# MPL3115A2_breakout.net
KiCad netlist of a schematic drawn in EAGLE
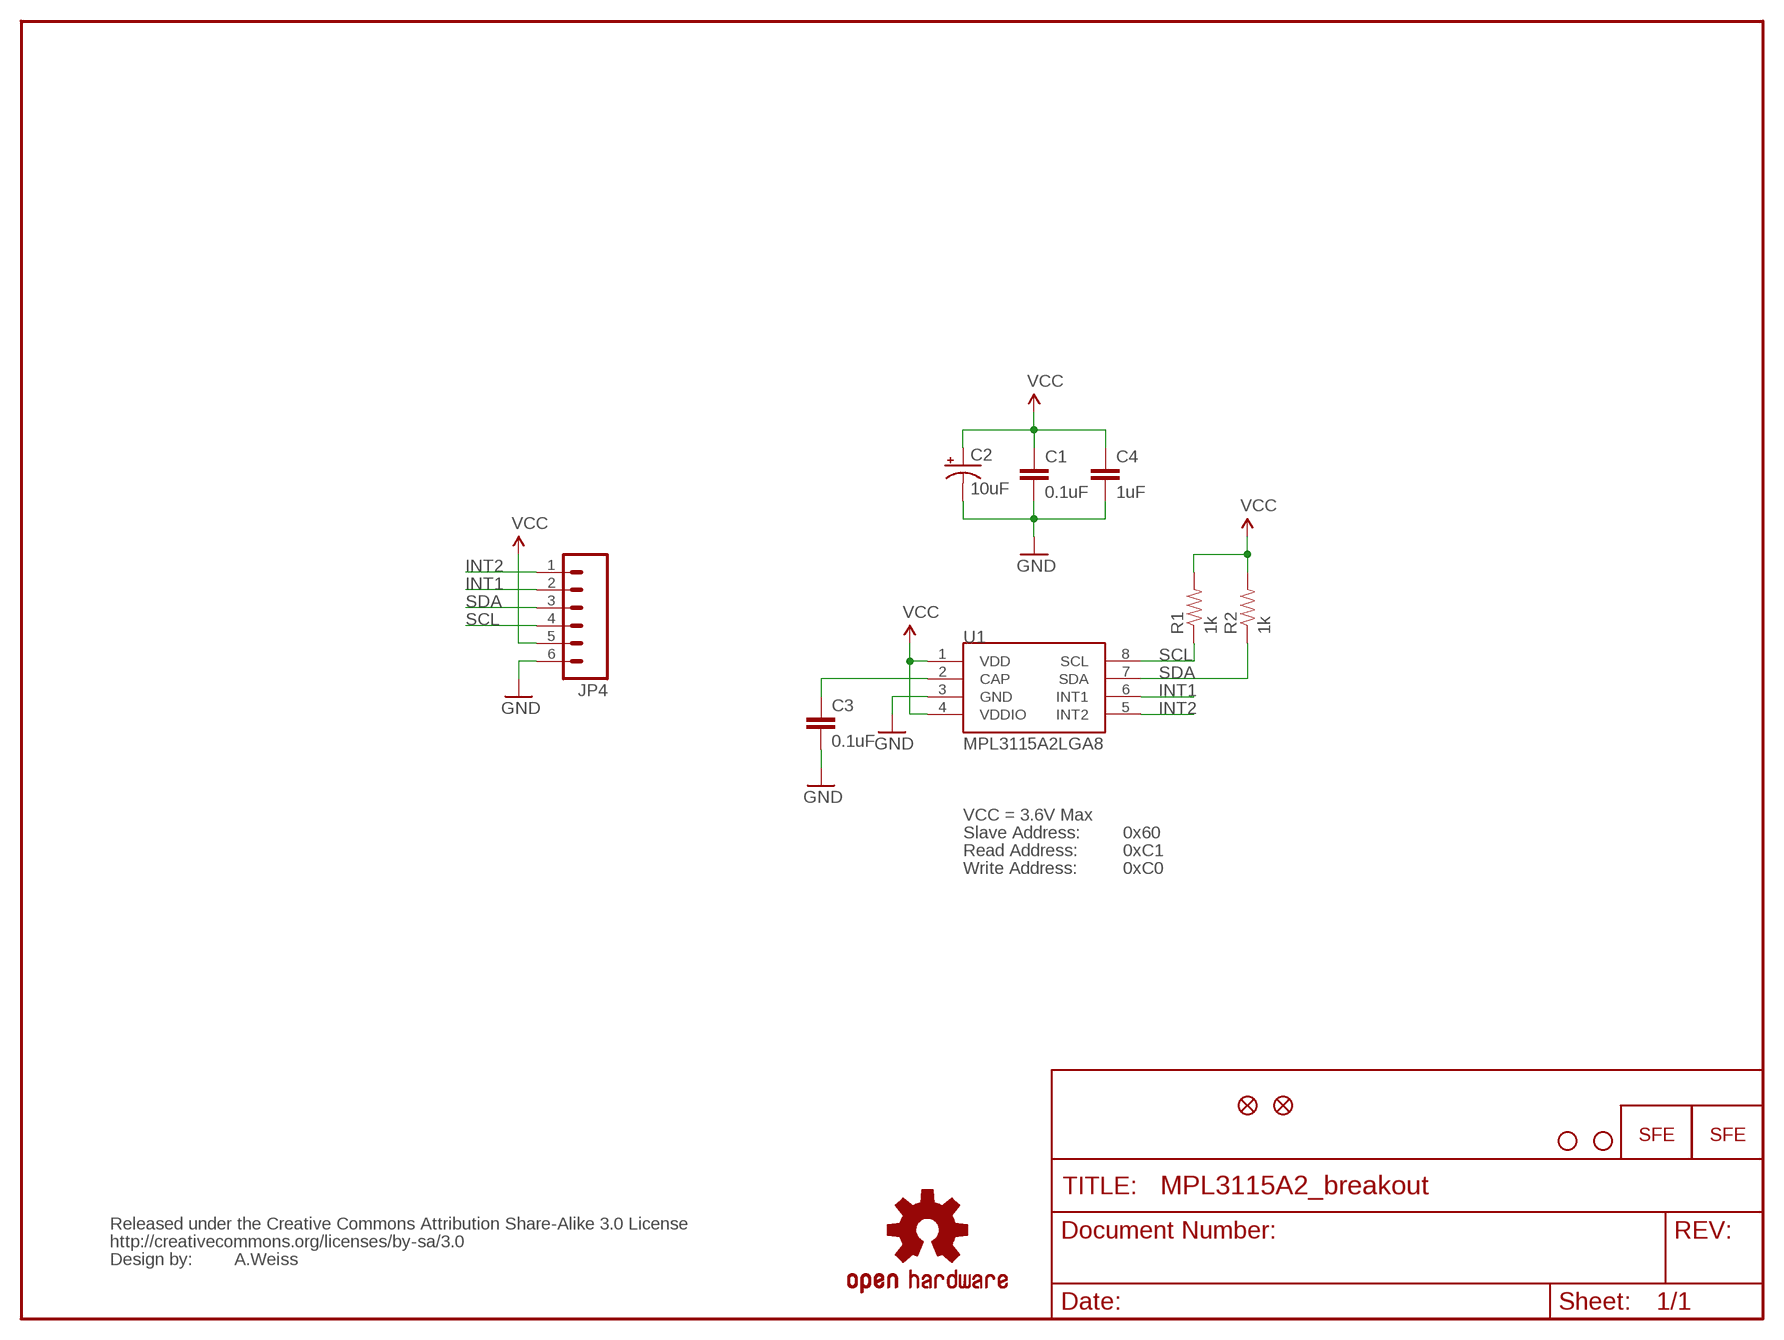
[diagram p0: schematic, sheet 1]

(export (version "E")
  (design (tool "Eeschema 10.0.6"))
  (components
    (comp (ref "C1")
      (value "0.1uF")
      (footprint "eagle-import:0402-CAP")
      (libsource (lib "eagle-import") (part "CAP0402-CAP"))
    )
    (comp (ref "C2")
      (value "10uF")
      (footprint "eagle-import:EIA3216")
      (libsource (lib "eagle-import") (part "CAP_POL1206"))
    )
    (comp (ref "C3")
      (value "0.1uF")
      (footprint "eagle-import:0402-CAP")
      (libsource (lib "eagle-import") (part "CAP0402-CAP"))
    )
    (comp (ref "C4")
      (value "1uF")
      (footprint "eagle-import:0402-CAP")
      (libsource (lib "eagle-import") (part "CAP0402-CAP"))
    )
    (comp (ref "JP1")
      (value "LOGO-SFESK")
      (footprint "eagle-import:SFE-LOGO-FLAME")
      (libsource (lib "eagle-import") (part "LOGO-SFESK"))
    )
    (comp (ref "JP2")
      (value "STAND-OFF")
      (footprint "eagle-import:STAND-OFF")
      (libsource (lib "eagle-import") (part "STAND-OFF"))
    )
    (comp (ref "JP3")
      (value "STAND-OFF")
      (footprint "eagle-import:STAND-OFF")
      (libsource (lib "eagle-import") (part "STAND-OFF"))
    )
    (comp (ref "JP4")
      (value "M06SIP")
      (footprint "eagle-import:1X06")
      (libsource (lib "eagle-import") (part "M06SIP"))
    )
    (comp (ref "JP5")
      (value "LOGO-SFESK")
      (footprint "eagle-import:SFE-LOGO-FLAME")
      (libsource (lib "eagle-import") (part "LOGO-SFESK"))
    )
    (comp (ref "JP6")
      (value "FIDUCIALUFIDUCIAL")
      (footprint "eagle-import:MICRO-FIDUCIAL")
      (libsource (lib "eagle-import") (part "FIDUCIALUFIDUCIAL"))
    )
    (comp (ref "JP7")
      (value "FIDUCIALUFIDUCIAL")
      (footprint "eagle-import:MICRO-FIDUCIAL")
      (libsource (lib "eagle-import") (part "FIDUCIALUFIDUCIAL"))
    )
    (comp (ref "R1")
      (value "1k")
      (footprint "eagle-import:0402-RES")
      (libsource (lib "eagle-import") (part "RESISTOR0402-RES"))
    )
    (comp (ref "R2")
      (value "1k")
      (footprint "eagle-import:0402-RES")
      (libsource (lib "eagle-import") (part "RESISTOR0402-RES"))
    )
    (comp (ref "U$1")
      (value "OSHW-LOGOS")
      (footprint "eagle-import:OSHW-LOGO-S")
      (libsource (lib "eagle-import") (part "OSHW-LOGOS"))
    )
    (comp (ref "U$2")
      (value "CREATIVE_COMMONS")
      (footprint "eagle-import:CREATIVE_COMMONS")
      (libsource (lib "eagle-import") (part "CREATIVE_COMMONS"))
    )
    (comp (ref "U1")
      (value "MPL3115A2LGA8")
      (footprint "eagle-import:LGA8")
      (libsource (lib "eagle-import") (part "MPL3115A2LGA8"))
    )
  )
  (nets
    (net (code "1") (name "/INT1") (class "Default")
      (node (ref "JP4") (pin "2") (pinfunction "2_2") (pintype "passive"))
      (node (ref "U1") (pin "6") (pinfunction "INT1_6") (pintype "bidirectional"))
    )
    (net (code "2") (name "/INT2") (class "Default")
      (node (ref "JP4") (pin "1") (pinfunction "1_1") (pintype "passive"))
      (node (ref "U1") (pin "5") (pinfunction "INT2_5") (pintype "bidirectional"))
    )
    (net (code "3") (name "/SCL") (class "Default")
      (node (ref "JP4") (pin "4") (pinfunction "4_4") (pintype "passive"))
      (node (ref "R1") (pin "1") (pinfunction "1_1") (pintype "passive"))
      (node (ref "U1") (pin "8") (pinfunction "SCL_8") (pintype "bidirectional"))
    )
    (net (code "4") (name "/SDA") (class "Default")
      (node (ref "JP4") (pin "3") (pinfunction "3_3") (pintype "passive"))
      (node (ref "R2") (pin "1") (pinfunction "1_1") (pintype "passive"))
      (node (ref "U1") (pin "7") (pinfunction "SDA_7") (pintype "bidirectional"))
    )
    (net (code "5") (name "GND") (class "Default")
      (node (ref "C1") (pin "2") (pinfunction "2_2") (pintype "passive"))
      (node (ref "C2") (pin "C") (pinfunction "-_C") (pintype "passive"))
      (node (ref "C3") (pin "2") (pinfunction "2_2") (pintype "passive"))
      (node (ref "C4") (pin "2") (pinfunction "2_2") (pintype "passive"))
      (node (ref "JP4") (pin "6") (pinfunction "6_6") (pintype "passive"))
      (node (ref "U1") (pin "3") (pinfunction "GND_3") (pintype "bidirectional"))
    )
    (net (code "6") (name "Net-(U1-CAP)") (class "Default")
      (node (ref "C3") (pin "1") (pinfunction "1_1") (pintype "passive"))
      (node (ref "U1") (pin "2") (pinfunction "CAP_2") (pintype "bidirectional"))
    )
    (net (code "7") (name "VCC") (class "Default")
      (node (ref "C1") (pin "1") (pinfunction "1_1") (pintype "passive"))
      (node (ref "C2") (pin "A") (pinfunction "+_A") (pintype "passive"))
      (node (ref "C4") (pin "1") (pinfunction "1_1") (pintype "passive"))
      (node (ref "JP4") (pin "5") (pinfunction "5_5") (pintype "passive"))
      (node (ref "R1") (pin "2") (pinfunction "2_2") (pintype "passive"))
      (node (ref "R2") (pin "2") (pinfunction "2_2") (pintype "passive"))
      (node (ref "U1") (pin "1") (pinfunction "VDD_1") (pintype "bidirectional"))
      (node (ref "U1") (pin "4") (pinfunction "VDDIO_4") (pintype "bidirectional"))
    )
  )
)
